# Qwiic_RFID_Tag.net
KiCad netlist of a schematic drawn in EAGLE
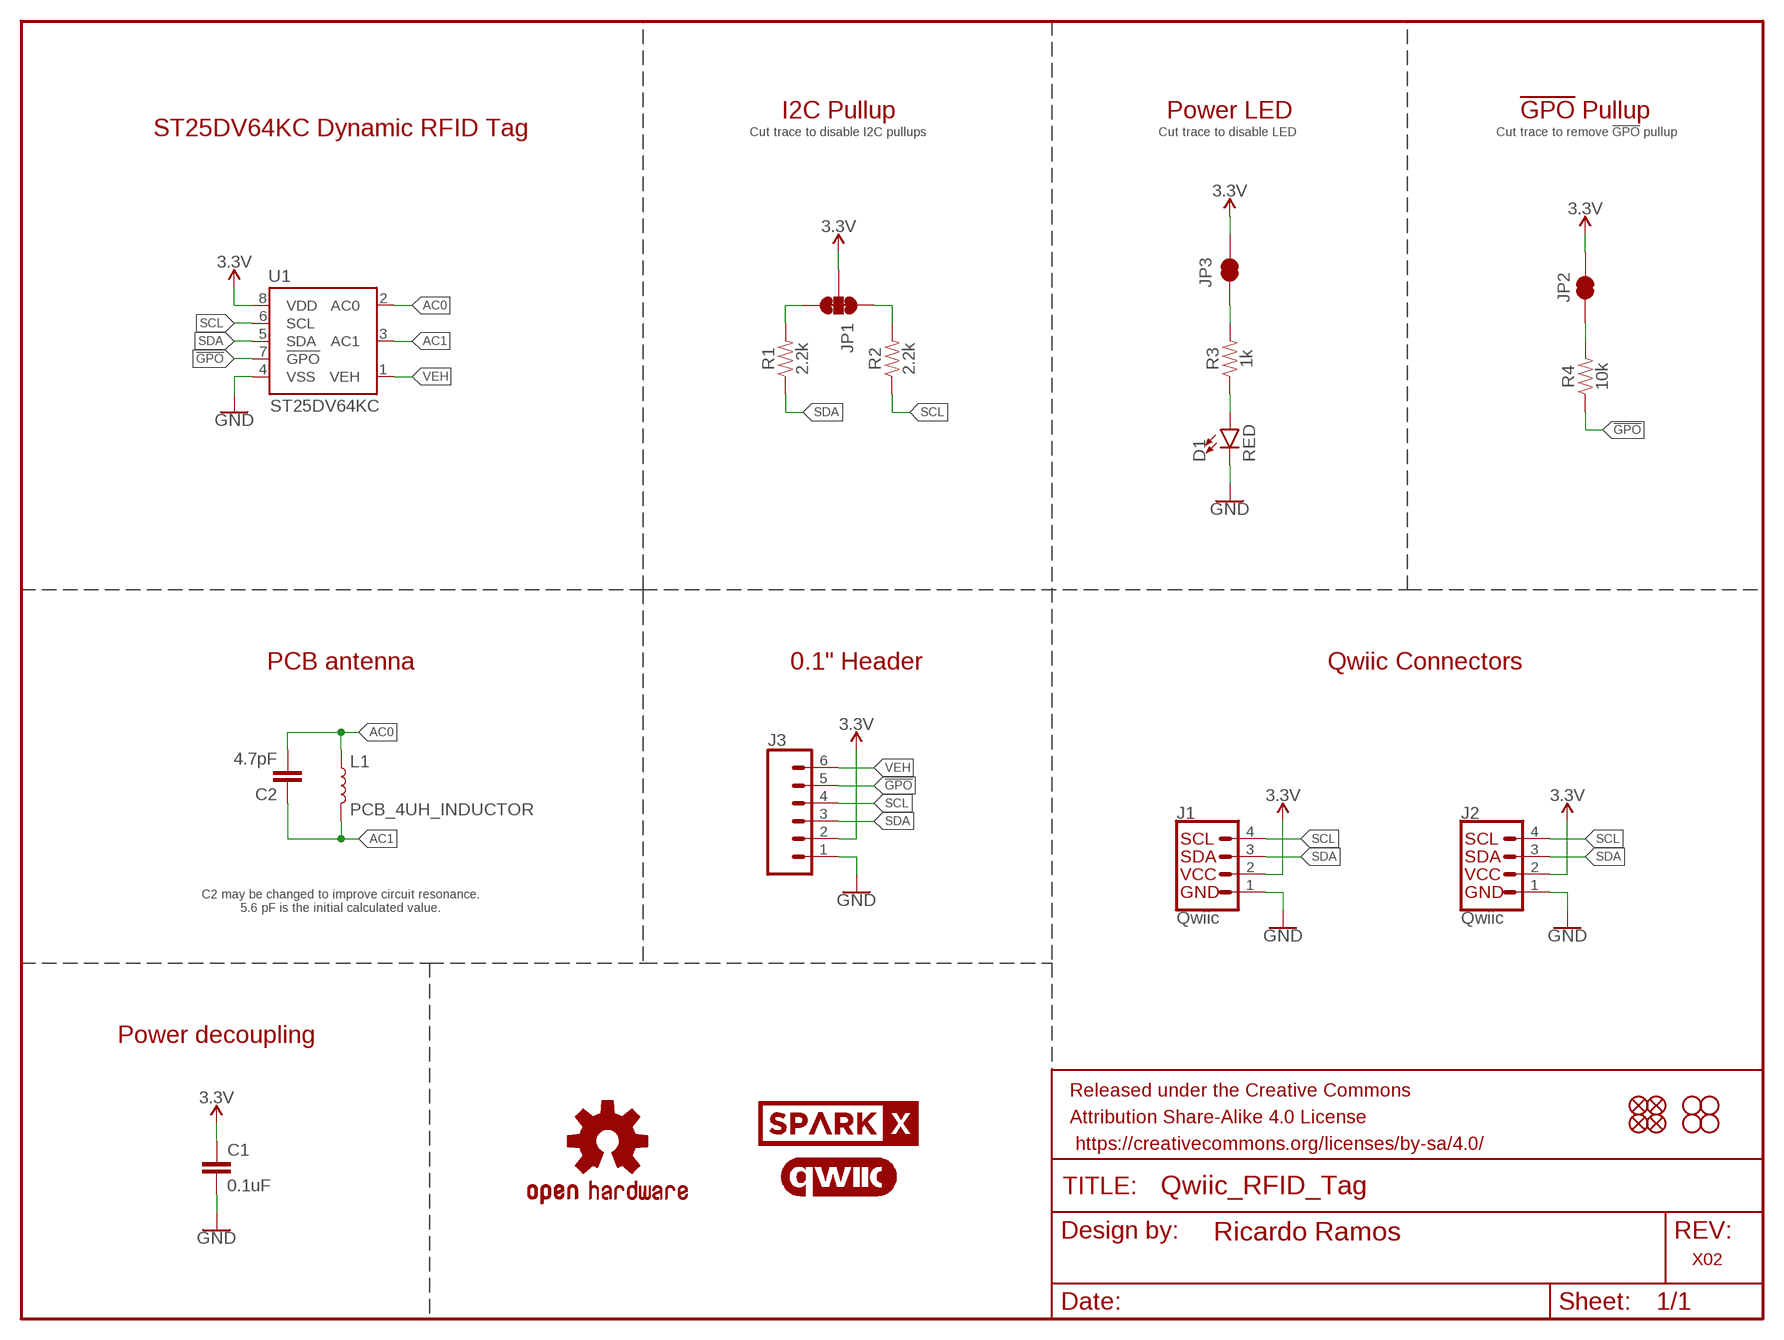
[diagram p0: schematic, sheet 1]

(export (version "E")
  (design (tool "Eeschema 10.0.6"))
  (components
    (comp (ref "C1")
      (value "0.1uF")
      (footprint "eagle-import:0603")
      (libsource (lib "eagle-import") (part "0.1UF-0603-25V-(+80/-20%)"))
    )
    (comp (ref "C2")
      (value "4.7pF")
      (footprint "eagle-import:0603")
      (libsource (lib "eagle-import") (part "4.7PF-0603-50V-5%"))
    )
    (comp (ref "D1")
      (value "RED")
      (footprint "eagle-import:LED-0603")
      (libsource (lib "eagle-import") (part "LED-RED0603"))
    )
    (comp (ref "FD1")
      (value "FIDUCIAL1X2")
      (footprint "eagle-import:FIDUCIAL-1X2")
      (libsource (lib "eagle-import") (part "FIDUCIAL1X2"))
    )
    (comp (ref "FD2")
      (value "FIDUCIAL1X2")
      (footprint "eagle-import:FIDUCIAL-1X2")
      (libsource (lib "eagle-import") (part "FIDUCIAL1X2"))
    )
    (comp (ref "FD3")
      (value "FIDUCIAL1X2")
      (footprint "eagle-import:FIDUCIAL-1X2")
      (libsource (lib "eagle-import") (part "FIDUCIAL1X2"))
    )
    (comp (ref "FD4")
      (value "FIDUCIAL1X2")
      (footprint "eagle-import:FIDUCIAL-1X2")
      (libsource (lib "eagle-import") (part "FIDUCIAL1X2"))
    )
    (comp (ref "FRAME1")
      (value "FRAME-LETTERNO_PACKAGE")
      (footprint "eagle-import:DUMMY")
      (fields
        (field (name "DESIGNER") "Ricardo Ramos")
        (field (name "REV") "X02")
        (field (name "VERSION") "x01")
        (field (name "DESIGNER_1") "Ricardo Ramos")
      )
      (libsource (lib "eagle-import") (part "FRAME-LETTERNO_PACKAGE"))
    )
    (comp (ref "H1")
      (value "STAND-OFF")
      (footprint "eagle-import:STAND-OFF")
      (libsource (lib "eagle-import") (part "STAND-OFF"))
    )
    (comp (ref "H2")
      (value "STAND-OFF")
      (footprint "eagle-import:STAND-OFF")
      (libsource (lib "eagle-import") (part "STAND-OFF"))
    )
    (comp (ref "H3")
      (value "STAND-OFF")
      (footprint "eagle-import:STAND-OFF")
      (libsource (lib "eagle-import") (part "STAND-OFF"))
    )
    (comp (ref "H4")
      (value "STAND-OFF")
      (footprint "eagle-import:STAND-OFF")
      (libsource (lib "eagle-import") (part "STAND-OFF"))
    )
    (comp (ref "J1")
      (value "Qwiic")
      (footprint "eagle-import:JST04_1MM_RA")
      (libsource (lib "eagle-import") (part "QWIIC_CONNECTORJS-1MM"))
    )
    (comp (ref "J2")
      (value "Qwiic")
      (footprint "eagle-import:JST04_1MM_RA")
      (libsource (lib "eagle-import") (part "QWIIC_CONNECTORJS-1MM"))
    )
    (comp (ref "J3")
      (value "CONN_06NO_SILK_FEMALE_PTH")
      (footprint "eagle-import:1X06_NO_SILK")
      (libsource (lib "eagle-import") (part "CONN_06NO_SILK_FEMALE_PTH"))
    )
    (comp (ref "JP1")
      (value "JUMPER-SMT_3_2-NC_TRACE_SILK")
      (footprint "eagle-import:SMT-JUMPER_3_2-NC_TRACE_SILK")
      (libsource (lib "eagle-import") (part "JUMPER-SMT_3_2-NC_TRACE_SILK"))
    )
    (comp (ref "JP2")
      (value "JUMPER-SMT_2_NC_TRACE_SILK")
      (footprint "eagle-import:SMT-JUMPER_2_NC_TRACE_SILK")
      (libsource (lib "eagle-import") (part "JUMPER-SMT_2_NC_TRACE_SILK"))
    )
    (comp (ref "JP3")
      (value "JUMPER-SMT_2_NC_TRACE_SILK")
      (footprint "eagle-import:SMT-JUMPER_2_NC_TRACE_SILK")
      (libsource (lib "eagle-import") (part "JUMPER-SMT_2_NC_TRACE_SILK"))
    )
    (comp (ref "L1")
      (value "PCB_4UH_INDUCTOR")
      (footprint "eagle-import:PCB_4UH_INDUCTOR")
      (libsource (lib "eagle-import") (part "PCB_4UH_INDUCTOR"))
    )
    (comp (ref "LOGO1")
      (value "OSHW-LOGOMINI")
      (footprint "eagle-import:OSHW-LOGO-MINI")
      (libsource (lib "eagle-import") (part "OSHW-LOGOMINI"))
    )
    (comp (ref "LOGO3")
      (value "QWIIC_LOGO_7MM")
      (footprint "eagle-import:QWIIC_7MM")
      (libsource (lib "eagle-import") (part "QWIIC_LOGO_7MM"))
    )
    (comp (ref "R1")
      (value "2.2k")
      (footprint "eagle-import:0603")
      (libsource (lib "eagle-import") (part "2.2KOHM-0603-1/10W-1%"))
    )
    (comp (ref "R2")
      (value "2.2k")
      (footprint "eagle-import:0603")
      (libsource (lib "eagle-import") (part "2.2KOHM-0603-1/10W-1%"))
    )
    (comp (ref "R3")
      (value "1k")
      (footprint "eagle-import:0603")
      (libsource (lib "eagle-import") (part "1KOHM-0603-1/10W-1%"))
    )
    (comp (ref "R4")
      (value "10k")
      (footprint "eagle-import:0603")
      (libsource (lib "eagle-import") (part "10KOHM-0603-1/10W-1%"))
    )
    (comp (ref "U$1")
      (value "SPARKX-LOGO5")
      (footprint "eagle-import:SPARKX-LARGE")
      (libsource (lib "eagle-import") (part "SPARKX-LOGO5"))
    )
    (comp (ref "U$2")
      (value "SPARKX-LOGO5")
      (footprint "eagle-import:SPARKX-LARGE")
      (libsource (lib "eagle-import") (part "SPARKX-LOGO5"))
    )
    (comp (ref "U1")
      (value "ST25DV64KC")
      (footprint "eagle-import:SO08")
      (libsource (lib "eagle-import") (part "ST25DV64KC"))
    )
  )
  (nets
    (net (code "1") (name "/~{GPO}") (class "Default")
      (node (ref "J3") (pin "5") (pinfunction "5_5") (pintype "passive"))
      (node (ref "R4") (pin "1") (pinfunction "1_1") (pintype "passive"))
      (node (ref "U1") (pin "7") (pinfunction "~{GPO}_7") (pintype "output"))
    )
    (net (code "2") (name "3.3V") (class "Default")
      (node (ref "C1") (pin "1") (pinfunction "1_1") (pintype "passive"))
      (node (ref "J1") (pin "2") (pinfunction "2_2") (pintype "power_in"))
      (node (ref "J2") (pin "2") (pinfunction "2_2") (pintype "power_in"))
      (node (ref "J3") (pin "2") (pinfunction "2_2") (pintype "passive"))
      (node (ref "JP1") (pin "2") (pinfunction "2_2") (pintype "passive"))
      (node (ref "JP2") (pin "2") (pinfunction "2_2") (pintype "passive"))
      (node (ref "JP3") (pin "2") (pinfunction "2_2") (pintype "passive"))
      (node (ref "U1") (pin "8") (pinfunction "VDD_8") (pintype "power_in"))
    )
    (net (code "3") (name "AC0") (class "Default")
      (node (ref "C2") (pin "2") (pinfunction "2_2") (pintype "passive"))
      (node (ref "L1") (pin "IN1") (pinfunction "1_IN1") (pintype "passive"))
      (node (ref "U1") (pin "2") (pinfunction "AC0_2") (pintype "bidirectional"))
    )
    (net (code "4") (name "AC1") (class "Default")
      (node (ref "C2") (pin "1") (pinfunction "1_1") (pintype "passive"))
      (node (ref "L1") (pin "IN2") (pinfunction "2_IN2") (pintype "passive"))
      (node (ref "U1") (pin "3") (pinfunction "AC1_3") (pintype "bidirectional"))
    )
    (net (code "5") (name "GND") (class "Default")
      (node (ref "C1") (pin "2") (pinfunction "2_2") (pintype "passive"))
      (node (ref "D1") (pin "C") (pinfunction "C_C") (pintype "passive"))
      (node (ref "J1") (pin "1") (pinfunction "1_1") (pintype "power_in"))
      (node (ref "J2") (pin "1") (pinfunction "1_1") (pintype "power_in"))
      (node (ref "J3") (pin "1") (pinfunction "1_1") (pintype "passive"))
      (node (ref "U1") (pin "4") (pinfunction "VSS_4") (pintype "power_in"))
    )
    (net (code "6") (name "Net-(D1-PadA)") (class "Default")
      (node (ref "D1") (pin "A") (pinfunction "A_A") (pintype "passive"))
      (node (ref "R3") (pin "1") (pinfunction "1_1") (pintype "passive"))
    )
    (net (code "7") (name "Net-(JP1-Pad1)") (class "Default")
      (node (ref "JP1") (pin "1") (pinfunction "1_1") (pintype "passive"))
      (node (ref "R2") (pin "2") (pinfunction "2_2") (pintype "passive"))
    )
    (net (code "8") (name "Net-(JP1-Pad3)") (class "Default")
      (node (ref "JP1") (pin "3") (pinfunction "3_3") (pintype "passive"))
      (node (ref "R1") (pin "2") (pinfunction "2_2") (pintype "passive"))
    )
    (net (code "9") (name "Net-(JP2-Pad1)") (class "Default")
      (node (ref "JP2") (pin "1") (pinfunction "1_1") (pintype "passive"))
      (node (ref "R4") (pin "2") (pinfunction "2_2") (pintype "passive"))
    )
    (net (code "10") (name "Net-(JP3-Pad1)") (class "Default")
      (node (ref "JP3") (pin "1") (pinfunction "1_1") (pintype "passive"))
      (node (ref "R3") (pin "2") (pinfunction "2_2") (pintype "passive"))
    )
    (net (code "11") (name "SCL") (class "Default")
      (node (ref "J1") (pin "4") (pinfunction "4_4") (pintype "passive"))
      (node (ref "J2") (pin "4") (pinfunction "4_4") (pintype "passive"))
      (node (ref "J3") (pin "4") (pinfunction "4_4") (pintype "passive"))
      (node (ref "R2") (pin "1") (pinfunction "1_1") (pintype "passive"))
      (node (ref "U1") (pin "6") (pinfunction "SCL_6") (pintype "bidirectional"))
    )
    (net (code "12") (name "SDA") (class "Default")
      (node (ref "J1") (pin "3") (pinfunction "3_3") (pintype "passive"))
      (node (ref "J2") (pin "3") (pinfunction "3_3") (pintype "passive"))
      (node (ref "J3") (pin "3") (pinfunction "3_3") (pintype "passive"))
      (node (ref "R1") (pin "1") (pinfunction "1_1") (pintype "passive"))
      (node (ref "U1") (pin "5") (pinfunction "SDA_5") (pintype "bidirectional"))
    )
    (net (code "13") (name "VEH") (class "Default")
      (node (ref "J3") (pin "6") (pinfunction "6_6") (pintype "passive"))
      (node (ref "U1") (pin "1") (pinfunction "VEH_1") (pintype "power_in"))
    )
  )
)
